# MainSchem.net
KiCad netlist of a schematic drawn in EAGLE
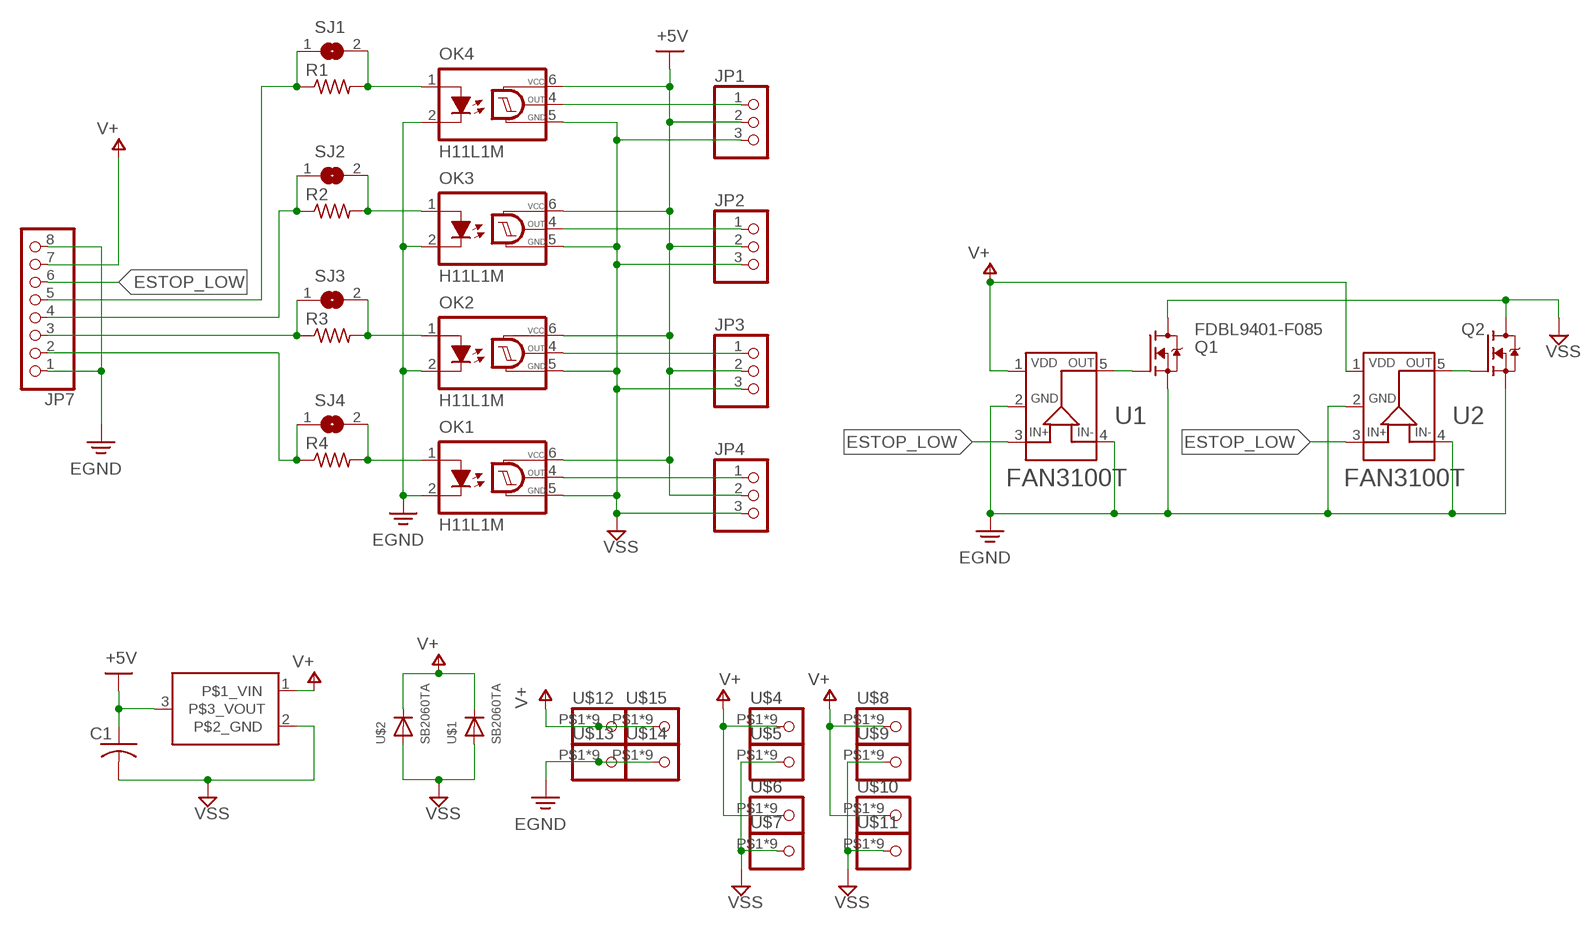
[diagram p0: schematic, sheet 1]

(export (version "E")
  (design (tool "Eeschema 10.0.6"))
  (components
    (comp (ref "C1")
      (value "C-US025-025X050")
      (footprint "eagle-import:C025-025X050")
      (libsource (lib "eagle-import") (part "C-US025-025X050"))
    )
    (comp (ref "JP1")
      (value "PINHD-1X3")
      (footprint "eagle-import:1X03")
      (libsource (lib "eagle-import") (part "PINHD-1X3"))
    )
    (comp (ref "JP2")
      (value "PINHD-1X3")
      (footprint "eagle-import:1X03")
      (libsource (lib "eagle-import") (part "PINHD-1X3"))
    )
    (comp (ref "JP3")
      (value "PINHD-1X3")
      (footprint "eagle-import:1X03")
      (libsource (lib "eagle-import") (part "PINHD-1X3"))
    )
    (comp (ref "JP4")
      (value "PINHD-1X3")
      (footprint "eagle-import:1X03")
      (libsource (lib "eagle-import") (part "PINHD-1X3"))
    )
    (comp (ref "JP7")
      (value "PINHD-1X8")
      (footprint "eagle-import:1X08")
      (libsource (lib "eagle-import") (part "PINHD-1X8"))
    )
    (comp (ref "OK1")
      (value "H11L1M")
      (footprint "eagle-import:DIL06")
      (fields (field (name "MF") "FAIRCHILD SEMICONDUCTOR") (field (name "MPN") "H11L1-M"))
      (libsource (lib "eagle-import") (part "H11LM1"))
    )
    (comp (ref "OK2")
      (value "H11L1M")
      (footprint "eagle-import:DIL06")
      (fields (field (name "MF") "FAIRCHILD SEMICONDUCTOR") (field (name "MPN") "H11L1-M"))
      (libsource (lib "eagle-import") (part "H11LM1"))
    )
    (comp (ref "OK3")
      (value "H11L1M")
      (footprint "eagle-import:DIL06")
      (fields (field (name "MF") "FAIRCHILD SEMICONDUCTOR") (field (name "MPN") "H11L1-M"))
      (libsource (lib "eagle-import") (part "H11LM1"))
    )
    (comp (ref "OK4")
      (value "H11L1M")
      (footprint "eagle-import:DIL06")
      (fields (field (name "MF") "FAIRCHILD SEMICONDUCTOR") (field (name "MPN") "H11L1-M"))
      (libsource (lib "eagle-import") (part "H11LM1"))
    )
    (comp (ref "Q1")
      (value "FDBL9401-F085")
      (footprint "eagle-import:MOSFET_FDBL86361-F085")
      (fields
        (field (name "DIGI-KEY_PART_NUMBER") "FDBL86361-F085CT-ND")
        (field (name "MF") "ON Semiconductor")
        (field (name "MP") "FDBL86361-F085")
      )
      (libsource (lib "eagle-import") (part "FDBL86361-F085"))
    )
    (comp (ref "Q2")
      (value "FDBL9401-F085")
      (footprint "eagle-import:MOSFET_FDBL86361-F085")
      (fields
        (field (name "DIGI-KEY_PART_NUMBER") "FDBL86361-F085CT-ND")
        (field (name "MF") "ON Semiconductor")
        (field (name "MP") "FDBL86361-F085")
      )
      (libsource (lib "eagle-import") (part "FDBL86361-F085"))
    )
    (comp (ref "R1")
      (value "R-US_0204/7")
      (footprint "eagle-import:0204_7")
      (libsource (lib "eagle-import") (part "R-US_0204/7"))
    )
    (comp (ref "R2")
      (value "R-US_0204/7")
      (footprint "eagle-import:0204_7")
      (libsource (lib "eagle-import") (part "R-US_0204/7"))
    )
    (comp (ref "R3")
      (value "R-US_0204/7")
      (footprint "eagle-import:0204_7")
      (libsource (lib "eagle-import") (part "R-US_0204/7"))
    )
    (comp (ref "R4")
      (value "R-US_0204/7")
      (footprint "eagle-import:0204_7")
      (libsource (lib "eagle-import") (part "R-US_0204/7"))
    )
    (comp (ref "SJ1") (value "SJ") (footprint "eagle-import:SJ") (libsource (lib "eagle-import") (part "SJ")))
    (comp (ref "SJ2") (value "SJ") (footprint "eagle-import:SJ") (libsource (lib "eagle-import") (part "SJ")))
    (comp (ref "SJ3") (value "SJ") (footprint "eagle-import:SJ") (libsource (lib "eagle-import") (part "SJ")))
    (comp (ref "SJ4") (value "SJ") (footprint "eagle-import:SJ") (libsource (lib "eagle-import") (part "SJ")))
    (comp (ref "U$1")
      (value "SB2060TA")
      (footprint "eagle-import:C4111-15")
      (libsource (lib "eagle-import") (part "GENERIC_DIODE_DO201AD"))
    )
    (comp (ref "U$2")
      (value "SB2060TA")
      (footprint "eagle-import:C4111-15")
      (libsource (lib "eagle-import") (part "GENERIC_DIODE_DO201AD"))
    )
    (comp (ref "U$3")
      (value "REGULATOR_5V")
      (footprint "eagle-import:TO220")
      (libsource (lib "eagle-import") (part "REGULATOR_5V"))
    )
    (comp (ref "U$4")
      (value "HIGH_CURRENT_WIRE_PAD")
      (footprint "eagle-import:HIGH_CURRENT_WIRE_PAD")
      (libsource (lib "eagle-import") (part "HIGH_CURRENT_WIRE_PAD"))
    )
    (comp (ref "U$5")
      (value "HIGH_CURRENT_WIRE_PAD")
      (footprint "eagle-import:HIGH_CURRENT_WIRE_PAD")
      (libsource (lib "eagle-import") (part "HIGH_CURRENT_WIRE_PAD"))
    )
    (comp (ref "U$6")
      (value "HIGH_CURRENT_WIRE_PAD")
      (footprint "eagle-import:HIGH_CURRENT_WIRE_PAD")
      (libsource (lib "eagle-import") (part "HIGH_CURRENT_WIRE_PAD"))
    )
    (comp (ref "U$7")
      (value "HIGH_CURRENT_WIRE_PAD")
      (footprint "eagle-import:HIGH_CURRENT_WIRE_PAD")
      (libsource (lib "eagle-import") (part "HIGH_CURRENT_WIRE_PAD"))
    )
    (comp (ref "U$8")
      (value "HIGH_CURRENT_WIRE_PAD")
      (footprint "eagle-import:HIGH_CURRENT_WIRE_PAD")
      (libsource (lib "eagle-import") (part "HIGH_CURRENT_WIRE_PAD"))
    )
    (comp (ref "U$9")
      (value "HIGH_CURRENT_WIRE_PAD")
      (footprint "eagle-import:HIGH_CURRENT_WIRE_PAD")
      (libsource (lib "eagle-import") (part "HIGH_CURRENT_WIRE_PAD"))
    )
    (comp (ref "U$10")
      (value "HIGH_CURRENT_WIRE_PAD")
      (footprint "eagle-import:HIGH_CURRENT_WIRE_PAD")
      (libsource (lib "eagle-import") (part "HIGH_CURRENT_WIRE_PAD"))
    )
    (comp (ref "U$11")
      (value "HIGH_CURRENT_WIRE_PAD")
      (footprint "eagle-import:HIGH_CURRENT_WIRE_PAD")
      (libsource (lib "eagle-import") (part "HIGH_CURRENT_WIRE_PAD"))
    )
    (comp (ref "U$12")
      (value "HIGH_CURRENT_WIRE_PAD")
      (footprint "eagle-import:HIGH_CURRENT_WIRE_PAD")
      (libsource (lib "eagle-import") (part "HIGH_CURRENT_WIRE_PAD"))
    )
    (comp (ref "U$13")
      (value "HIGH_CURRENT_WIRE_PAD")
      (footprint "eagle-import:HIGH_CURRENT_WIRE_PAD")
      (libsource (lib "eagle-import") (part "HIGH_CURRENT_WIRE_PAD"))
    )
    (comp (ref "U$14")
      (value "HIGH_CURRENT_WIRE_PAD")
      (footprint "eagle-import:HIGH_CURRENT_WIRE_PAD")
      (libsource (lib "eagle-import") (part "HIGH_CURRENT_WIRE_PAD"))
    )
    (comp (ref "U$15")
      (value "HIGH_CURRENT_WIRE_PAD")
      (footprint "eagle-import:HIGH_CURRENT_WIRE_PAD")
      (libsource (lib "eagle-import") (part "HIGH_CURRENT_WIRE_PAD"))
    )
    (comp (ref "U1")
      (value "FAN3100T")
      (footprint "eagle-import:SOT23-5")
      (libsource (lib "eagle-import") (part "FAN3100T"))
    )
    (comp (ref "U2")
      (value "FAN3100T")
      (footprint "eagle-import:SOT23-5")
      (libsource (lib "eagle-import") (part "FAN3100T"))
    )
  )
  (nets
    (net (code "1") (name "+5V") (class "Default")
      (node (ref "C1") (pin "1") (pinfunction "1_1") (pintype "passive"))
      (node (ref "JP1") (pin "2") (pinfunction "2_2") (pintype "passive"))
      (node (ref "JP2") (pin "2") (pinfunction "2_2") (pintype "passive"))
      (node (ref "JP3") (pin "2") (pinfunction "2_2") (pintype "passive"))
      (node (ref "JP4") (pin "2") (pinfunction "2_2") (pintype "passive"))
      (node (ref "OK1") (pin "6") (pinfunction "VCC_6") (pintype "power_in"))
      (node (ref "OK2") (pin "6") (pinfunction "VCC_6") (pintype "power_in"))
      (node (ref "OK3") (pin "6") (pinfunction "VCC_6") (pintype "power_in"))
      (node (ref "OK4") (pin "6") (pinfunction "VCC_6") (pintype "power_in"))
      (node (ref "U$3") (pin "3") (pinfunction "P$3_VOUT_3") (pintype "output"))
    )
    (net (code "2") (name "EGND") (class "Default")
      (node (ref "JP7") (pin "1") (pinfunction "1_1") (pintype "passive"))
      (node (ref "JP7") (pin "8") (pinfunction "8_8") (pintype "passive"))
      (node (ref "OK1") (pin "2") (pinfunction "C_2") (pintype "passive"))
      (node (ref "OK2") (pin "2") (pinfunction "C_2") (pintype "passive"))
      (node (ref "OK3") (pin "2") (pinfunction "C_2") (pintype "passive"))
      (node (ref "OK4") (pin "2") (pinfunction "C_2") (pintype "passive"))
      (node (ref "Q1") (pin "2") (pinfunction "S_2") (pintype "passive"))
      (node (ref "Q1") (pin "3") (pinfunction "S_3") (pintype "passive"))
      (node (ref "Q1") (pin "4") (pinfunction "S_4") (pintype "passive"))
      (node (ref "Q1") (pin "5") (pinfunction "S_5") (pintype "passive"))
      (node (ref "Q1") (pin "6") (pinfunction "S_6") (pintype "passive"))
      (node (ref "Q1") (pin "7") (pinfunction "S_7") (pintype "passive"))
      (node (ref "Q1") (pin "8") (pinfunction "S_8") (pintype "passive"))
      (node (ref "Q2") (pin "2") (pinfunction "S_2") (pintype "passive"))
      (node (ref "Q2") (pin "3") (pinfunction "S_3") (pintype "passive"))
      (node (ref "Q2") (pin "4") (pinfunction "S_4") (pintype "passive"))
      (node (ref "Q2") (pin "5") (pinfunction "S_5") (pintype "passive"))
      (node (ref "Q2") (pin "6") (pinfunction "S_6") (pintype "passive"))
      (node (ref "Q2") (pin "7") (pinfunction "S_7") (pintype "passive"))
      (node (ref "Q2") (pin "8") (pinfunction "S_8") (pintype "passive"))
      (node (ref "U$13") (pin "P$1") (pinfunction "1_P$1") (pintype "passive"))
      (node (ref "U$13") (pin "P$2") (pinfunction "1_P$2") (pintype "passive"))
      (node (ref "U$13") (pin "P$3") (pinfunction "1_P$3") (pintype "passive"))
      (node (ref "U$13") (pin "P$4") (pinfunction "1_P$4") (pintype "passive"))
      (node (ref "U$13") (pin "P$5") (pinfunction "1_P$5") (pintype "passive"))
      (node (ref "U$13") (pin "P$6") (pinfunction "1_P$6") (pintype "passive"))
      (node (ref "U$13") (pin "P$7") (pinfunction "1_P$7") (pintype "passive"))
      (node (ref "U$13") (pin "P$8") (pinfunction "1_P$8") (pintype "passive"))
      (node (ref "U$13") (pin "P$9") (pinfunction "1_P$9") (pintype "passive"))
      (node (ref "U$14") (pin "P$1") (pinfunction "1_P$1") (pintype "passive"))
      (node (ref "U$14") (pin "P$2") (pinfunction "1_P$2") (pintype "passive"))
      (node (ref "U$14") (pin "P$3") (pinfunction "1_P$3") (pintype "passive"))
      (node (ref "U$14") (pin "P$4") (pinfunction "1_P$4") (pintype "passive"))
      (node (ref "U$14") (pin "P$5") (pinfunction "1_P$5") (pintype "passive"))
      (node (ref "U$14") (pin "P$6") (pinfunction "1_P$6") (pintype "passive"))
      (node (ref "U$14") (pin "P$7") (pinfunction "1_P$7") (pintype "passive"))
      (node (ref "U$14") (pin "P$8") (pinfunction "1_P$8") (pintype "passive"))
      (node (ref "U$14") (pin "P$9") (pinfunction "1_P$9") (pintype "passive"))
      (node (ref "U1") (pin "2") (pinfunction "GND_2") (pintype "power_in"))
      (node (ref "U1") (pin "4") (pinfunction "IN-_4") (pintype "input"))
      (node (ref "U2") (pin "2") (pinfunction "GND_2") (pintype "power_in"))
      (node (ref "U2") (pin "4") (pinfunction "IN-_4") (pintype "input"))
    )
    (net (code "3") (name "ESTOP_LOW") (class "Default")
      (node (ref "JP7") (pin "6") (pinfunction "6_6") (pintype "passive"))
      (node (ref "U1") (pin "3") (pinfunction "IN+_3") (pintype "input"))
      (node (ref "U2") (pin "3") (pinfunction "IN+_3") (pintype "input"))
    )
    (net (code "4") (name "Net-(JP7-Pad2)") (class "Default")
      (node (ref "JP7") (pin "2") (pinfunction "2_2") (pintype "passive"))
      (node (ref "R4") (pin "1") (pinfunction "1_1") (pintype "passive"))
      (node (ref "SJ4") (pin "1") (pinfunction "1_1") (pintype "passive"))
    )
    (net (code "5") (name "Net-(JP7-Pad3)") (class "Default")
      (node (ref "JP7") (pin "3") (pinfunction "3_3") (pintype "passive"))
      (node (ref "R3") (pin "1") (pinfunction "1_1") (pintype "passive"))
      (node (ref "SJ3") (pin "1") (pinfunction "1_1") (pintype "passive"))
    )
    (net (code "6") (name "Net-(JP7-Pad4)") (class "Default")
      (node (ref "JP7") (pin "4") (pinfunction "4_4") (pintype "passive"))
      (node (ref "R2") (pin "1") (pinfunction "1_1") (pintype "passive"))
      (node (ref "SJ2") (pin "1") (pinfunction "1_1") (pintype "passive"))
    )
    (net (code "7") (name "Net-(JP7-Pad5)") (class "Default")
      (node (ref "JP7") (pin "5") (pinfunction "5_5") (pintype "passive"))
      (node (ref "R1") (pin "1") (pinfunction "1_1") (pintype "passive"))
      (node (ref "SJ1") (pin "1") (pinfunction "1_1") (pintype "passive"))
    )
    (net (code "8") (name "Net-(OK1-A)") (class "Default")
      (node (ref "OK1") (pin "1") (pinfunction "A_1") (pintype "passive"))
      (node (ref "R4") (pin "2") (pinfunction "2_2") (pintype "passive"))
      (node (ref "SJ4") (pin "2") (pinfunction "2_2") (pintype "passive"))
    )
    (net (code "9") (name "Net-(OK1-OUT)") (class "Default")
      (node (ref "JP4") (pin "1") (pinfunction "1_1") (pintype "passive"))
      (node (ref "OK1") (pin "4") (pinfunction "OUT_4") (pintype "output"))
    )
    (net (code "10") (name "Net-(OK2-A)") (class "Default")
      (node (ref "OK2") (pin "1") (pinfunction "A_1") (pintype "passive"))
      (node (ref "R3") (pin "2") (pinfunction "2_2") (pintype "passive"))
      (node (ref "SJ3") (pin "2") (pinfunction "2_2") (pintype "passive"))
    )
    (net (code "11") (name "Net-(OK2-OUT)") (class "Default")
      (node (ref "JP3") (pin "1") (pinfunction "1_1") (pintype "passive"))
      (node (ref "OK2") (pin "4") (pinfunction "OUT_4") (pintype "output"))
    )
    (net (code "12") (name "Net-(OK3-A)") (class "Default")
      (node (ref "OK3") (pin "1") (pinfunction "A_1") (pintype "passive"))
      (node (ref "R2") (pin "2") (pinfunction "2_2") (pintype "passive"))
      (node (ref "SJ2") (pin "2") (pinfunction "2_2") (pintype "passive"))
    )
    (net (code "13") (name "Net-(OK3-OUT)") (class "Default")
      (node (ref "JP2") (pin "1") (pinfunction "1_1") (pintype "passive"))
      (node (ref "OK3") (pin "4") (pinfunction "OUT_4") (pintype "output"))
    )
    (net (code "14") (name "Net-(OK4-A)") (class "Default")
      (node (ref "OK4") (pin "1") (pinfunction "A_1") (pintype "passive"))
      (node (ref "R1") (pin "2") (pinfunction "2_2") (pintype "passive"))
      (node (ref "SJ1") (pin "2") (pinfunction "2_2") (pintype "passive"))
    )
    (net (code "15") (name "Net-(OK4-OUT)") (class "Default")
      (node (ref "JP1") (pin "1") (pinfunction "1_1") (pintype "passive"))
      (node (ref "OK4") (pin "4") (pinfunction "OUT_4") (pintype "output"))
    )
    (net (code "16") (name "Net-(Q1-G)") (class "Default")
      (node (ref "Q1") (pin "1") (pinfunction "G_1") (pintype "passive"))
      (node (ref "U1") (pin "5") (pinfunction "OUT_5") (pintype "output"))
    )
    (net (code "17") (name "Net-(Q2-G)") (class "Default")
      (node (ref "Q2") (pin "1") (pinfunction "G_1") (pintype "passive"))
      (node (ref "U2") (pin "5") (pinfunction "OUT_5") (pintype "output"))
    )
    (net (code "18") (name "V+") (class "Default")
      (node (ref "JP7") (pin "7") (pinfunction "7_7") (pintype "passive"))
      (node (ref "U$1") (pin "C") (pinfunction "C_C") (pintype "passive"))
      (node (ref "U$10") (pin "P$1") (pinfunction "1_P$1") (pintype "passive"))
      (node (ref "U$10") (pin "P$2") (pinfunction "1_P$2") (pintype "passive"))
      (node (ref "U$10") (pin "P$3") (pinfunction "1_P$3") (pintype "passive"))
      (node (ref "U$10") (pin "P$4") (pinfunction "1_P$4") (pintype "passive"))
      (node (ref "U$10") (pin "P$5") (pinfunction "1_P$5") (pintype "passive"))
      (node (ref "U$10") (pin "P$6") (pinfunction "1_P$6") (pintype "passive"))
      (node (ref "U$10") (pin "P$7") (pinfunction "1_P$7") (pintype "passive"))
      (node (ref "U$10") (pin "P$8") (pinfunction "1_P$8") (pintype "passive"))
      (node (ref "U$10") (pin "P$9") (pinfunction "1_P$9") (pintype "passive"))
      (node (ref "U$12") (pin "P$1") (pinfunction "1_P$1") (pintype "passive"))
      (node (ref "U$12") (pin "P$2") (pinfunction "1_P$2") (pintype "passive"))
      (node (ref "U$12") (pin "P$3") (pinfunction "1_P$3") (pintype "passive"))
      (node (ref "U$12") (pin "P$4") (pinfunction "1_P$4") (pintype "passive"))
      (node (ref "U$12") (pin "P$5") (pinfunction "1_P$5") (pintype "passive"))
      (node (ref "U$12") (pin "P$6") (pinfunction "1_P$6") (pintype "passive"))
      (node (ref "U$12") (pin "P$7") (pinfunction "1_P$7") (pintype "passive"))
      (node (ref "U$12") (pin "P$8") (pinfunction "1_P$8") (pintype "passive"))
      (node (ref "U$12") (pin "P$9") (pinfunction "1_P$9") (pintype "passive"))
      (node (ref "U$15") (pin "P$1") (pinfunction "1_P$1") (pintype "passive"))
      (node (ref "U$15") (pin "P$2") (pinfunction "1_P$2") (pintype "passive"))
      (node (ref "U$15") (pin "P$3") (pinfunction "1_P$3") (pintype "passive"))
      (node (ref "U$15") (pin "P$4") (pinfunction "1_P$4") (pintype "passive"))
      (node (ref "U$15") (pin "P$5") (pinfunction "1_P$5") (pintype "passive"))
      (node (ref "U$15") (pin "P$6") (pinfunction "1_P$6") (pintype "passive"))
      (node (ref "U$15") (pin "P$7") (pinfunction "1_P$7") (pintype "passive"))
      (node (ref "U$15") (pin "P$8") (pinfunction "1_P$8") (pintype "passive"))
      (node (ref "U$15") (pin "P$9") (pinfunction "1_P$9") (pintype "passive"))
      (node (ref "U$2") (pin "C") (pinfunction "C_C") (pintype "passive"))
      (node (ref "U$3") (pin "1") (pinfunction "P$1_VIN_1") (pintype "input"))
      (node (ref "U$4") (pin "P$1") (pinfunction "1_P$1") (pintype "passive"))
      (node (ref "U$4") (pin "P$2") (pinfunction "1_P$2") (pintype "passive"))
      (node (ref "U$4") (pin "P$3") (pinfunction "1_P$3") (pintype "passive"))
      (node (ref "U$4") (pin "P$4") (pinfunction "1_P$4") (pintype "passive"))
      (node (ref "U$4") (pin "P$5") (pinfunction "1_P$5") (pintype "passive"))
      (node (ref "U$4") (pin "P$6") (pinfunction "1_P$6") (pintype "passive"))
      (node (ref "U$4") (pin "P$7") (pinfunction "1_P$7") (pintype "passive"))
      (node (ref "U$4") (pin "P$8") (pinfunction "1_P$8") (pintype "passive"))
      (node (ref "U$4") (pin "P$9") (pinfunction "1_P$9") (pintype "passive"))
      (node (ref "U$6") (pin "P$1") (pinfunction "1_P$1") (pintype "passive"))
      (node (ref "U$6") (pin "P$2") (pinfunction "1_P$2") (pintype "passive"))
      (node (ref "U$6") (pin "P$3") (pinfunction "1_P$3") (pintype "passive"))
      (node (ref "U$6") (pin "P$4") (pinfunction "1_P$4") (pintype "passive"))
      (node (ref "U$6") (pin "P$5") (pinfunction "1_P$5") (pintype "passive"))
      (node (ref "U$6") (pin "P$6") (pinfunction "1_P$6") (pintype "passive"))
      (node (ref "U$6") (pin "P$7") (pinfunction "1_P$7") (pintype "passive"))
      (node (ref "U$6") (pin "P$8") (pinfunction "1_P$8") (pintype "passive"))
      (node (ref "U$6") (pin "P$9") (pinfunction "1_P$9") (pintype "passive"))
      (node (ref "U$8") (pin "P$1") (pinfunction "1_P$1") (pintype "passive"))
      (node (ref "U$8") (pin "P$2") (pinfunction "1_P$2") (pintype "passive"))
      (node (ref "U$8") (pin "P$3") (pinfunction "1_P$3") (pintype "passive"))
      (node (ref "U$8") (pin "P$4") (pinfunction "1_P$4") (pintype "passive"))
      (node (ref "U$8") (pin "P$5") (pinfunction "1_P$5") (pintype "passive"))
      (node (ref "U$8") (pin "P$6") (pinfunction "1_P$6") (pintype "passive"))
      (node (ref "U$8") (pin "P$7") (pinfunction "1_P$7") (pintype "passive"))
      (node (ref "U$8") (pin "P$8") (pinfunction "1_P$8") (pintype "passive"))
      (node (ref "U$8") (pin "P$9") (pinfunction "1_P$9") (pintype "passive"))
      (node (ref "U1") (pin "1") (pinfunction "VDD_1") (pintype "power_in"))
      (node (ref "U2") (pin "1") (pinfunction "VDD_1") (pintype "power_in"))
    )
    (net (code "19") (name "VSS") (class "Default")
      (node (ref "C1") (pin "2") (pinfunction "2_2") (pintype "passive"))
      (node (ref "JP1") (pin "3") (pinfunction "3_3") (pintype "passive"))
      (node (ref "JP2") (pin "3") (pinfunction "3_3") (pintype "passive"))
      (node (ref "JP3") (pin "3") (pinfunction "3_3") (pintype "passive"))
      (node (ref "JP4") (pin "3") (pinfunction "3_3") (pintype "passive"))
      (node (ref "OK1") (pin "5") (pinfunction "GND_5") (pintype "power_in"))
      (node (ref "OK2") (pin "5") (pinfunction "GND_5") (pintype "power_in"))
      (node (ref "OK3") (pin "5") (pinfunction "GND_5") (pintype "power_in"))
      (node (ref "OK4") (pin "5") (pinfunction "GND_5") (pintype "power_in"))
      (node (ref "Q1") (pin "9_1") (pinfunction "D_9_1") (pintype "passive"))
      (node (ref "Q1") (pin "9_2") (pinfunction "D_9_2") (pintype "passive"))
      (node (ref "Q1") (pin "9_3") (pinfunction "D_9_3") (pintype "passive"))
      (node (ref "Q1") (pin "9_4") (pinfunction "D_9_4") (pintype "passive"))
      (node (ref "Q2") (pin "9_1") (pinfunction "D_9_1") (pintype "passive"))
      (node (ref "Q2") (pin "9_2") (pinfunction "D_9_2") (pintype "passive"))
      (node (ref "Q2") (pin "9_3") (pinfunction "D_9_3") (pintype "passive"))
      (node (ref "Q2") (pin "9_4") (pinfunction "D_9_4") (pintype "passive"))
      (node (ref "U$1") (pin "A") (pinfunction "A_A") (pintype "passive"))
      (node (ref "U$11") (pin "P$1") (pinfunction "1_P$1") (pintype "passive"))
      (node (ref "U$11") (pin "P$2") (pinfunction "1_P$2") (pintype "passive"))
      (node (ref "U$11") (pin "P$3") (pinfunction "1_P$3") (pintype "passive"))
      (node (ref "U$11") (pin "P$4") (pinfunction "1_P$4") (pintype "passive"))
      (node (ref "U$11") (pin "P$5") (pinfunction "1_P$5") (pintype "passive"))
      (node (ref "U$11") (pin "P$6") (pinfunction "1_P$6") (pintype "passive"))
      (node (ref "U$11") (pin "P$7") (pinfunction "1_P$7") (pintype "passive"))
      (node (ref "U$11") (pin "P$8") (pinfunction "1_P$8") (pintype "passive"))
      (node (ref "U$11") (pin "P$9") (pinfunction "1_P$9") (pintype "passive"))
      (node (ref "U$2") (pin "A") (pinfunction "A_A") (pintype "passive"))
      (node (ref "U$3") (pin "2") (pinfunction "P$2_GND_2") (pintype "bidirectional"))
      (node (ref "U$5") (pin "P$1") (pinfunction "1_P$1") (pintype "passive"))
      (node (ref "U$5") (pin "P$2") (pinfunction "1_P$2") (pintype "passive"))
      (node (ref "U$5") (pin "P$3") (pinfunction "1_P$3") (pintype "passive"))
      (node (ref "U$5") (pin "P$4") (pinfunction "1_P$4") (pintype "passive"))
      (node (ref "U$5") (pin "P$5") (pinfunction "1_P$5") (pintype "passive"))
      (node (ref "U$5") (pin "P$6") (pinfunction "1_P$6") (pintype "passive"))
      (node (ref "U$5") (pin "P$7") (pinfunction "1_P$7") (pintype "passive"))
      (node (ref "U$5") (pin "P$8") (pinfunction "1_P$8") (pintype "passive"))
      (node (ref "U$5") (pin "P$9") (pinfunction "1_P$9") (pintype "passive"))
      (node (ref "U$7") (pin "P$1") (pinfunction "1_P$1") (pintype "passive"))
      (node (ref "U$7") (pin "P$2") (pinfunction "1_P$2") (pintype "passive"))
      (node (ref "U$7") (pin "P$3") (pinfunction "1_P$3") (pintype "passive"))
      (node (ref "U$7") (pin "P$4") (pinfunction "1_P$4") (pintype "passive"))
      (node (ref "U$7") (pin "P$5") (pinfunction "1_P$5") (pintype "passive"))
      (node (ref "U$7") (pin "P$6") (pinfunction "1_P$6") (pintype "passive"))
      (node (ref "U$7") (pin "P$7") (pinfunction "1_P$7") (pintype "passive"))
      (node (ref "U$7") (pin "P$8") (pinfunction "1_P$8") (pintype "passive"))
      (node (ref "U$7") (pin "P$9") (pinfunction "1_P$9") (pintype "passive"))
      (node (ref "U$9") (pin "P$1") (pinfunction "1_P$1") (pintype "passive"))
      (node (ref "U$9") (pin "P$2") (pinfunction "1_P$2") (pintype "passive"))
      (node (ref "U$9") (pin "P$3") (pinfunction "1_P$3") (pintype "passive"))
      (node (ref "U$9") (pin "P$4") (pinfunction "1_P$4") (pintype "passive"))
      (node (ref "U$9") (pin "P$5") (pinfunction "1_P$5") (pintype "passive"))
      (node (ref "U$9") (pin "P$6") (pinfunction "1_P$6") (pintype "passive"))
      (node (ref "U$9") (pin "P$7") (pinfunction "1_P$7") (pintype "passive"))
      (node (ref "U$9") (pin "P$8") (pinfunction "1_P$8") (pintype "passive"))
      (node (ref "U$9") (pin "P$9") (pinfunction "1_P$9") (pintype "passive"))
    )
  )
)
